# clocking.net
KiCad netlist of a schematic drawn in Altium Designer
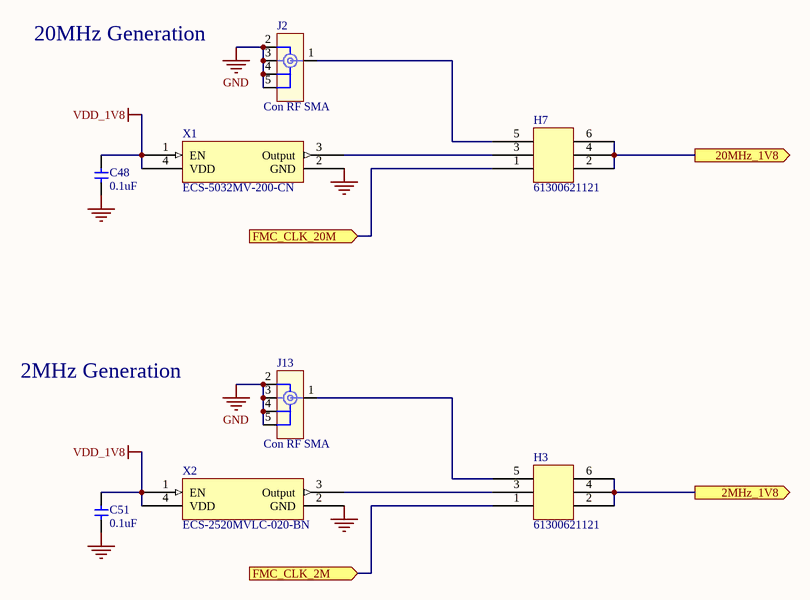
[diagram p0: clocking.SchDoc]

(export (version "E")
  (design (tool "Eeschema 10.0.6"))
  (components
    (comp (ref "C48")
      (value "0.1uF")
      (footprint "BWRC:0603")
      (description "0.1uF 0402")
      (libsource (lib "BWRC") (part "DISCRETE_C"))
    )
    (comp (ref "C51")
      (value "0.1uF")
      (footprint "BWRC:0603")
      (description "0.1uF 0402")
      (libsource (lib "BWRC") (part "DISCRETE_C"))
    )
    (comp (ref "H3")
      (value "61300621121")
      (footprint "CON-006-100-300X200/2X3-POST")
      (libsource (lib "schematic") (part "61300621121"))
    )
    (comp (ref "H7")
      (value "61300621121")
      (footprint "CON-006-100-300X200/2X3-POST")
      (libsource (lib "schematic") (part "61300621121"))
    )
    (comp (ref "J2")
      (value "Con RF SMA")
      (footprint "CON-001-7.0X7.0/ALL-THT-SMA-ST")
      (libsource (lib "BWRC") (part "CON_RF_SMA"))
    )
    (comp (ref "J13")
      (value "Con RF SMA")
      (footprint "CON-001-7.0X7.0/ALL-THT-SMA-ST")
      (libsource (lib "BWRC") (part "CON_RF_SMA"))
    )
    (comp (ref "X1")
      (value "ECS-5032MV-200-CN")
      (footprint "XTAL-04-5.0X3.2")
      (description "20 MHz HCMOS Oscillator, 1.6 - 3.6V")
      (libsource (lib "schematic") (part "ECS-5032MV-200-CN"))
    )
    (comp (ref "X2")
      (value "ECS-2520MVLC-020-BN")
      (footprint "XTAL-04-2.5X2.0")
      (description "2MHz CMOS Oscillator, 1.6 - 3.6V")
      (libsource (lib "schematic") (part "ECS-2520MVLC-020-BN"))
    )
  )
  (nets
    (net (code "1") (name "/2MHz_1V8") (class "Default")
      (node (ref "H3") (pin "2") (pintype "passive"))
      (node (ref "H3") (pin "4") (pintype "passive"))
      (node (ref "H3") (pin "6") (pintype "passive"))
    )
    (net (code "2") (name "/20MHz_1V8") (class "Default")
      (node (ref "H7") (pin "2") (pintype "passive"))
      (node (ref "H7") (pin "4") (pintype "passive"))
      (node (ref "H7") (pin "6") (pintype "passive"))
    )
    (net (code "3") (name "/FMC_CLK_2M") (class "Default") (node (ref "H3") (pin "1") (pintype "passive")))
    (net (code "4") (name "/FMC_CLK_20M") (class "Default") (node (ref "H7") (pin "1") (pintype "passive")))
    (net (code "5") (name "GND") (class "Default")
      (node (ref "C48") (pin "2") (pinfunction "2_2") (pintype "passive"))
      (node (ref "C51") (pin "2") (pinfunction "2_2") (pintype "passive"))
      (node (ref "J13") (pin "2") (pinfunction "2_2") (pintype "passive"))
      (node (ref "J13") (pin "3") (pinfunction "3_3") (pintype "passive"))
      (node (ref "J13") (pin "4") (pinfunction "4_4") (pintype "passive"))
      (node (ref "J13") (pin "5") (pinfunction "5_5") (pintype "passive"))
      (node (ref "J2") (pin "2") (pinfunction "2_2") (pintype "passive"))
      (node (ref "J2") (pin "3") (pinfunction "3_3") (pintype "passive"))
      (node (ref "J2") (pin "4") (pinfunction "4_4") (pintype "passive"))
      (node (ref "J2") (pin "5") (pinfunction "5_5") (pintype "passive"))
      (node (ref "X1") (pin "2") (pinfunction "GND_2") (pintype "power_in"))
      (node (ref "X2") (pin "2") (pinfunction "GND_2") (pintype "power_in"))
    )
    (net (code "6") (name "Net-(H3-Pad5)") (class "Default")
      (node (ref "H3") (pin "5") (pintype "passive"))
      (node (ref "J13") (pin "1") (pinfunction "1_1") (pintype "passive"))
    )
    (net (code "7") (name "Net-(H7-Pad5)") (class "Default")
      (node (ref "H7") (pin "5") (pintype "passive"))
      (node (ref "J2") (pin "1") (pinfunction "1_1") (pintype "passive"))
    )
    (net (code "8") (name "Net-(X1-Output)") (class "Default")
      (node (ref "H7") (pin "3") (pintype "passive"))
      (node (ref "X1") (pin "3") (pinfunction "Output_3") (pintype "output"))
    )
    (net (code "9") (name "Net-(X2-Output)") (class "Default")
      (node (ref "H3") (pin "3") (pintype "passive"))
      (node (ref "X2") (pin "3") (pinfunction "Output_3") (pintype "output"))
    )
    (net (code "10") (name "VDD_1V8") (class "Default")
      (node (ref "C48") (pin "1") (pinfunction "1_1") (pintype "passive"))
      (node (ref "C51") (pin "1") (pinfunction "1_1") (pintype "passive"))
      (node (ref "X1") (pin "1") (pinfunction "EN_1") (pintype "input"))
      (node (ref "X1") (pin "4") (pinfunction "VDD_4") (pintype "power_in"))
      (node (ref "X2") (pin "1") (pinfunction "EN_1") (pintype "input"))
      (node (ref "X2") (pin "4") (pinfunction "VDD_4") (pintype "power_in"))
    )
  )
)
